# Isolators_HV_6W.net
KiCad netlist of a schematic drawn in Altium Designer
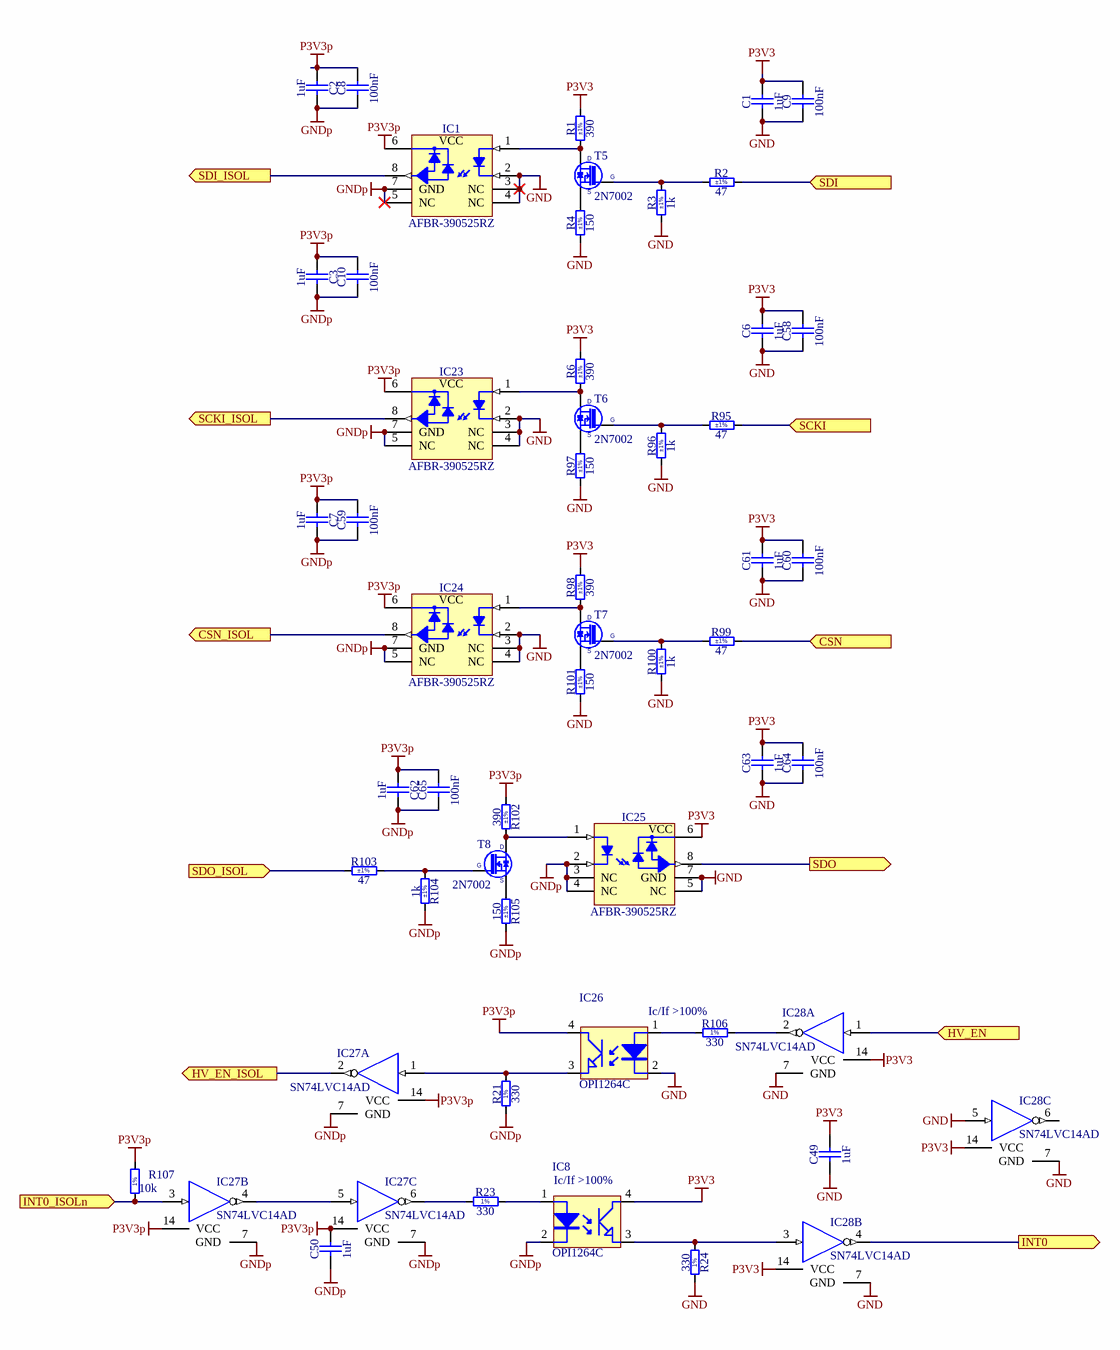
[diagram p0: Isolators_HV_6W.SchDoc]

(export (version "E")
  (design (tool "Eeschema 10.0.6"))
  (components
    (comp (ref "C1")
      (value "1uF")
      (footprint "CAPC1005X55N")
      (description "Non-polarised capacitor")
      (fields
        (field (name "PART NUMBER") "CC0402_1UF_16V_10%_X5R")
        (field (name "VOLTAGE") "16V")
        (field (name "AUTHOR") "CERN DEM JLC")
      )
      (libsource (lib "Capacitors") (part "Capacitor - non polarized"))
    )
    (comp (ref "C2")
      (value "1uF")
      (footprint "CAPC1005X55N")
      (description "Non-polarised capacitor")
      (fields
        (field (name "PART NUMBER") "CC0402_1UF_16V_10%_X5R")
        (field (name "VOLTAGE") "16V")
        (field (name "AUTHOR") "CERN DEM JLC")
      )
      (libsource (lib "Capacitors") (part "Capacitor - non polarized"))
    )
    (comp (ref "C3")
      (value "1uF")
      (footprint "CAPC1005X55N")
      (description "Non-polarised capacitor")
      (fields
        (field (name "PART NUMBER") "CC0402_1UF_16V_10%_X5R")
        (field (name "VOLTAGE") "16V")
        (field (name "AUTHOR") "CERN DEM JLC")
      )
      (libsource (lib "Capacitors") (part "Capacitor - non polarized"))
    )
    (comp (ref "C6")
      (value "1uF")
      (footprint "CAPC1005X55N")
      (description "Non-polarised capacitor")
      (fields
        (field (name "PART NUMBER") "CC0402_1UF_16V_10%_X5R")
        (field (name "VOLTAGE") "16V")
        (field (name "AUTHOR") "CERN DEM JLC")
      )
      (libsource (lib "Capacitors") (part "Capacitor - non polarized"))
    )
    (comp (ref "C7")
      (value "1uF")
      (footprint "CAPC1005X55N")
      (description "Non-polarised capacitor")
      (fields
        (field (name "PART NUMBER") "CC0402_1UF_16V_10%_X5R")
        (field (name "VOLTAGE") "16V")
        (field (name "AUTHOR") "CERN DEM JLC")
      )
      (libsource (lib "Capacitors") (part "Capacitor - non polarized"))
    )
    (comp (ref "C8")
      (value "100nF")
      (footprint "CAPC1005X55N")
      (description "Non-polarised capacitor")
      (fields
        (field (name "PART NUMBER") "CC0402_100NF_16V_10%_X5R")
        (field (name "VOLTAGE") "16V")
        (field (name "AUTHOR") "CERN DEM JLC")
      )
      (libsource (lib "Capacitors") (part "Capacitor - non polarized"))
    )
    (comp (ref "C9")
      (value "100nF")
      (footprint "CAPC1005X55N")
      (description "Non-polarised capacitor")
      (fields
        (field (name "PART NUMBER") "CC0402_100NF_16V_10%_X5R")
        (field (name "VOLTAGE") "16V")
        (field (name "AUTHOR") "CERN DEM JLC")
      )
      (libsource (lib "Capacitors") (part "Capacitor - non polarized"))
    )
    (comp (ref "C10")
      (value "100nF")
      (footprint "CAPC1005X55N")
      (description "Non-polarised capacitor")
      (fields
        (field (name "PART NUMBER") "CC0402_100NF_16V_10%_X5R")
        (field (name "VOLTAGE") "16V")
        (field (name "AUTHOR") "CERN DEM JLC")
      )
      (libsource (lib "Capacitors") (part "Capacitor - non polarized"))
    )
    (comp (ref "C49")
      (value "1uF")
      (footprint "CAPC1005X55N")
      (description "Non-polarised capacitor")
      (fields
        (field (name "PART NUMBER") "CC0402_1UF_16V_10%_X5R")
        (field (name "VOLTAGE") "16V")
        (field (name "AUTHOR") "CERN DEM JLC")
      )
      (libsource (lib "Capacitors") (part "Capacitor - non polarized"))
    )
    (comp (ref "C50")
      (value "1uF")
      (footprint "CAPC1005X55N")
      (description "Non-polarised capacitor")
      (fields
        (field (name "PART NUMBER") "CC0402_1UF_16V_10%_X5R")
        (field (name "VOLTAGE") "16V")
        (field (name "AUTHOR") "CERN DEM JLC")
      )
      (libsource (lib "Capacitors") (part "Capacitor - non polarized"))
    )
    (comp (ref "C58")
      (value "100nF")
      (footprint "CAPC1005X55N")
      (description "Non-polarised capacitor")
      (fields
        (field (name "PART NUMBER") "CC0402_100NF_16V_10%_X5R")
        (field (name "VOLTAGE") "16V")
        (field (name "AUTHOR") "CERN DEM JLC")
      )
      (libsource (lib "Capacitors") (part "Capacitor - non polarized"))
    )
    (comp (ref "C59")
      (value "100nF")
      (footprint "CAPC1005X55N")
      (description "Non-polarised capacitor")
      (fields
        (field (name "PART NUMBER") "CC0402_100NF_16V_10%_X5R")
        (field (name "VOLTAGE") "16V")
        (field (name "AUTHOR") "CERN DEM JLC")
      )
      (libsource (lib "Capacitors") (part "Capacitor - non polarized"))
    )
    (comp (ref "C60")
      (value "100nF")
      (footprint "CAPC1005X55N")
      (description "Non-polarised capacitor")
      (fields
        (field (name "PART NUMBER") "CC0402_100NF_16V_10%_X5R")
        (field (name "VOLTAGE") "16V")
        (field (name "AUTHOR") "CERN DEM JLC")
      )
      (libsource (lib "Capacitors") (part "Capacitor - non polarized"))
    )
    (comp (ref "C61")
      (value "1uF")
      (footprint "CAPC1005X55N")
      (description "Non-polarised capacitor")
      (fields
        (field (name "PART NUMBER") "CC0402_1UF_16V_10%_X5R")
        (field (name "VOLTAGE") "16V")
        (field (name "AUTHOR") "CERN DEM JLC")
      )
      (libsource (lib "Capacitors") (part "Capacitor - non polarized"))
    )
    (comp (ref "C62")
      (value "1uF")
      (footprint "CAPC1005X55N")
      (description "Non-polarised capacitor")
      (fields
        (field (name "PART NUMBER") "CC0402_1UF_16V_10%_X5R")
        (field (name "VOLTAGE") "16V")
        (field (name "AUTHOR") "CERN DEM JLC")
      )
      (libsource (lib "Capacitors") (part "Capacitor - non polarized"))
    )
    (comp (ref "C63")
      (value "1uF")
      (footprint "CAPC1005X55N")
      (description "Non-polarised capacitor")
      (fields
        (field (name "PART NUMBER") "CC0402_1UF_16V_10%_X5R")
        (field (name "VOLTAGE") "16V")
        (field (name "AUTHOR") "CERN DEM JLC")
      )
      (libsource (lib "Capacitors") (part "Capacitor - non polarized"))
    )
    (comp (ref "C64")
      (value "100nF")
      (footprint "CAPC1005X55N")
      (description "Non-polarised capacitor")
      (fields
        (field (name "PART NUMBER") "CC0402_100NF_16V_10%_X5R")
        (field (name "VOLTAGE") "16V")
        (field (name "AUTHOR") "CERN DEM JLC")
      )
      (libsource (lib "Capacitors") (part "Capacitor - non polarized"))
    )
    (comp (ref "C65")
      (value "100nF")
      (footprint "CAPC1005X55N")
      (description "Non-polarised capacitor")
      (fields
        (field (name "PART NUMBER") "CC0402_100NF_16V_10%_X5R")
        (field (name "VOLTAGE") "16V")
        (field (name "AUTHOR") "CERN DEM JLC")
      )
      (libsource (lib "Capacitors") (part "Capacitor - non polarized"))
    )
    (comp (ref "IC1")
      (value "AFBR-390525RZ")
      (footprint "BROADCOM_AFBR-390525RZ")
      (description "High Voltage Galvanic Insulation Link for DC to 5MBaud")
      (fields (field (name "MANUFACTURER") "BROADCOM") (field (name "AUTHOR") "CERN DEM HF"))
      (libsource (lib "") (part "AFBR-3905XXRZ_1"))
    )
    (comp (ref "IC8")
      (value "OPI1264C")
      (footprint "OPI1264C")
      (description "10kV opto-coupler")
      (libsource (lib "LIBRARY_SCH") (part "OPTO-OPI1264C"))
    )
    (comp (ref "IC23")
      (value "AFBR-390525RZ")
      (footprint "BROADCOM_AFBR-390525RZ")
      (description "High Voltage Galvanic Insulation Link for DC to 5MBaud")
      (fields (field (name "MANUFACTURER") "BROADCOM") (field (name "AUTHOR") "CERN DEM HF"))
      (libsource (lib "") (part "AFBR-3905XXRZ_1"))
    )
    (comp (ref "IC24")
      (value "AFBR-390525RZ")
      (footprint "BROADCOM_AFBR-390525RZ")
      (description "High Voltage Galvanic Insulation Link for DC to 5MBaud")
      (fields (field (name "MANUFACTURER") "BROADCOM") (field (name "AUTHOR") "CERN DEM HF"))
      (libsource (lib "") (part "AFBR-3905XXRZ_1"))
    )
    (comp (ref "IC25")
      (value "AFBR-390525RZ")
      (footprint "BROADCOM_AFBR-390525RZ")
      (description "High Voltage Galvanic Insulation Link for DC to 5MBaud")
      (fields (field (name "MANUFACTURER") "BROADCOM") (field (name "AUTHOR") "CERN DEM HF"))
      (libsource (lib "ICs And Semiconductors") (part "AFBR-3905XXRZ"))
    )
    (comp (ref "IC26")
      (value "OPI1264C")
      (footprint "OPI1264C")
      (description "10kV opto-coupler")
      (libsource (lib "") (part "OPTO-OPI1264C_1"))
    )
    (comp (ref "IC27")
      (value "SN74LVC14AD")
      (footprint "SOIC127P600X175-14N")
      (description "Hex Schmitt-Trigger Inverter")
      (fields (field (name "MANUFACTURER") "TEXAS INSTRUMENTS") (field (name "AUTHOR") "CERN DEM JMW"))
      (libsource (lib "ICs And Semiconductors") (part "7414"))
    )
    (comp (ref "IC28")
      (value "SN74LVC14AD")
      (footprint "SOIC127P600X175-14N")
      (description "Hex Schmitt-Trigger Inverter")
      (fields (field (name "MANUFACTURER") "TEXAS INSTRUMENTS") (field (name "AUTHOR") "CERN DEM JMW"))
      (libsource (lib "ICs And Semiconductors") (part "7414"))
    )
    (comp (ref "R1")
      (value "390")
      (footprint "RESC1608X55N")
      (description "Resistor - 1%")
      (fields
        (field (name "TOLERANCE") "±1%")
        (field (name "PART NUMBER") "R0603_390R_1%_0.1W_100PPM")
        (field (name "POWER") "0.1W")
        (field (name "AUTHOR") "CERN DEM JLC")
      )
      (libsource (lib "Resistors") (part "Resistor - 1%"))
    )
    (comp (ref "R2")
      (value "47")
      (footprint "RESC1005X40N")
      (description "Resistor - 1%")
      (fields
        (field (name "TOLERANCE") "±1%")
        (field (name "PART NUMBER") "R0402_47R_1%_0.0625W_100PPM")
        (field (name "POWER") "0.0625W")
        (field (name "AUTHOR") "CERN DEM JLC")
      )
      (libsource (lib "Resistors") (part "Resistor - 1%"))
    )
    (comp (ref "R3")
      (value "1k")
      (footprint "RESC1005X40N")
      (description "Resistor - 1%")
      (fields
        (field (name "TOLERANCE") "±1%")
        (field (name "PART NUMBER") "R0402_1K_1%_0.0625W_100PPM")
        (field (name "POWER") "0.0625W")
        (field (name "AUTHOR") "CERN DEM JLC")
      )
      (libsource (lib "Resistors") (part "Resistor - 1%"))
    )
    (comp (ref "R4")
      (value "150")
      (footprint "RESC1608X55N")
      (description "Resistor - 1%")
      (fields
        (field (name "TOLERANCE") "±1%")
        (field (name "PART NUMBER") "R0603_150R_1%_0.1W_100PPM")
        (field (name "POWER") "0.1W")
        (field (name "AUTHOR") "CERN DEM JLC")
      )
      (libsource (lib "Resistors") (part "Resistor - 1%"))
    )
    (comp (ref "R6")
      (value "390")
      (footprint "RESC1608X55N")
      (description "Resistor - 1%")
      (fields
        (field (name "TOLERANCE") "±1%")
        (field (name "PART NUMBER") "R0603_390R_1%_0.1W_100PPM")
        (field (name "POWER") "0.1W")
        (field (name "AUTHOR") "CERN DEM JLC")
      )
      (libsource (lib "Resistors") (part "Resistor - 1%"))
    )
    (comp (ref "R21")
      (value "330")
      (footprint "RESC1005X40N")
      (description "Resistor - 1%")
      (fields
        (field (name "PART NUMBER") "R0402_330R_1%_0.0625W_100PPM")
        (field (name "POWER") "0.0625W")
        (field (name "AUTHOR") "CERN DEM JLC")
      )
      (libsource (lib "") (part "Resistor - 1%_1"))
    )
    (comp (ref "R23")
      (value "330")
      (footprint "RESC1005X40N")
      (description "Resistor - 1%")
      (fields
        (field (name "PART NUMBER") "R0402_330R_1%_0.0625W_100PPM")
        (field (name "POWER") "0.0625W")
        (field (name "AUTHOR") "CERN DEM JLC")
      )
      (libsource (lib "") (part "Resistor - 1%_1"))
    )
    (comp (ref "R24")
      (value "330")
      (footprint "RESC1005X40N")
      (description "Resistor - 1%")
      (fields
        (field (name "PART NUMBER") "R0402_330R_1%_0.0625W_100PPM")
        (field (name "POWER") "0.0625W")
        (field (name "AUTHOR") "CERN DEM JLC")
      )
      (libsource (lib "") (part "Resistor - 1%_1"))
    )
    (comp (ref "R95")
      (value "47")
      (footprint "RESC1005X40N")
      (description "Resistor - 1%")
      (fields
        (field (name "TOLERANCE") "±1%")
        (field (name "PART NUMBER") "R0402_47R_1%_0.0625W_100PPM")
        (field (name "POWER") "0.0625W")
        (field (name "AUTHOR") "CERN DEM JLC")
      )
      (libsource (lib "Resistors") (part "Resistor - 1%"))
    )
    (comp (ref "R96")
      (value "1k")
      (footprint "RESC1005X40N")
      (description "Resistor - 1%")
      (fields
        (field (name "TOLERANCE") "±1%")
        (field (name "PART NUMBER") "R0402_1K_1%_0.0625W_100PPM")
        (field (name "POWER") "0.0625W")
        (field (name "AUTHOR") "CERN DEM JLC")
      )
      (libsource (lib "Resistors") (part "Resistor - 1%"))
    )
    (comp (ref "R97")
      (value "150")
      (footprint "RESC1608X55N")
      (description "Resistor - 1%")
      (fields
        (field (name "TOLERANCE") "±1%")
        (field (name "PART NUMBER") "R0603_150R_1%_0.1W_100PPM")
        (field (name "POWER") "0.1W")
        (field (name "AUTHOR") "CERN DEM JLC")
      )
      (libsource (lib "Resistors") (part "Resistor - 1%"))
    )
    (comp (ref "R98")
      (value "390")
      (footprint "RESC1608X55N")
      (description "Resistor - 1%")
      (fields
        (field (name "TOLERANCE") "±1%")
        (field (name "PART NUMBER") "R0603_390R_1%_0.1W_100PPM")
        (field (name "POWER") "0.1W")
        (field (name "AUTHOR") "CERN DEM JLC")
      )
      (libsource (lib "Resistors") (part "Resistor - 1%"))
    )
    (comp (ref "R99")
      (value "47")
      (footprint "RESC1005X40N")
      (description "Resistor - 1%")
      (fields
        (field (name "TOLERANCE") "±1%")
        (field (name "PART NUMBER") "R0402_47R_1%_0.0625W_100PPM")
        (field (name "POWER") "0.0625W")
        (field (name "AUTHOR") "CERN DEM JLC")
      )
      (libsource (lib "Resistors") (part "Resistor - 1%"))
    )
    (comp (ref "R100")
      (value "1k")
      (footprint "RESC1005X40N")
      (description "Resistor - 1%")
      (fields
        (field (name "TOLERANCE") "±1%")
        (field (name "PART NUMBER") "R0402_1K_1%_0.0625W_100PPM")
        (field (name "POWER") "0.0625W")
        (field (name "AUTHOR") "CERN DEM JLC")
      )
      (libsource (lib "Resistors") (part "Resistor - 1%"))
    )
    (comp (ref "R101")
      (value "150")
      (footprint "RESC1608X55N")
      (description "Resistor - 1%")
      (fields
        (field (name "TOLERANCE") "±1%")
        (field (name "PART NUMBER") "R0603_150R_1%_0.1W_100PPM")
        (field (name "POWER") "0.1W")
        (field (name "AUTHOR") "CERN DEM JLC")
      )
      (libsource (lib "Resistors") (part "Resistor - 1%"))
    )
    (comp (ref "R102")
      (value "390")
      (footprint "RESC1608X55N")
      (description "Resistor - 1%")
      (fields
        (field (name "TOLERANCE") "±1%")
        (field (name "PART NUMBER") "R0603_390R_1%_0.1W_100PPM")
        (field (name "POWER") "0.1W")
        (field (name "AUTHOR") "CERN DEM JLC")
      )
      (libsource (lib "Resistors") (part "Resistor - 1%"))
    )
    (comp (ref "R103")
      (value "47")
      (footprint "RESC1005X40N")
      (description "Resistor - 1%")
      (fields
        (field (name "TOLERANCE") "±1%")
        (field (name "PART NUMBER") "R0402_47R_1%_0.0625W_100PPM")
        (field (name "POWER") "0.0625W")
        (field (name "AUTHOR") "CERN DEM JLC")
      )
      (libsource (lib "Resistors") (part "Resistor - 1%"))
    )
    (comp (ref "R104")
      (value "1k")
      (footprint "RESC1005X40N")
      (description "Resistor - 1%")
      (fields
        (field (name "TOLERANCE") "±1%")
        (field (name "PART NUMBER") "R0402_1K_1%_0.0625W_100PPM")
        (field (name "POWER") "0.0625W")
        (field (name "AUTHOR") "CERN DEM JLC")
      )
      (libsource (lib "Resistors") (part "Resistor - 1%"))
    )
    (comp (ref "R105")
      (value "150")
      (footprint "RESC1608X55N")
      (description "Resistor - 1%")
      (fields
        (field (name "TOLERANCE") "±1%")
        (field (name "PART NUMBER") "R0603_150R_1%_0.1W_100PPM")
        (field (name "POWER") "0.1W")
        (field (name "AUTHOR") "CERN DEM JLC")
      )
      (libsource (lib "Resistors") (part "Resistor - 1%"))
    )
    (comp (ref "R106")
      (value "330")
      (footprint "RESC1005X40N")
      (description "Resistor - 1%")
      (fields
        (field (name "PART NUMBER") "R0402_330R_1%_0.0625W_100PPM")
        (field (name "POWER") "0.0625W")
        (field (name "AUTHOR") "CERN DEM JLC")
      )
      (libsource (lib "") (part "Resistor - 1%_1"))
    )
    (comp (ref "R107")
      (value "10k")
      (footprint "RESC1005X40N")
      (description "Resistor - 1%")
      (fields
        (field (name "PART NUMBER") "R0402_10K_1%_0.0625W_100PPM")
        (field (name "POWER") "0.0625W")
        (field (name "AUTHOR") "CERN DEM JLC")
      )
      (libsource (lib "") (part "Resistor - 1%_1"))
    )
    (comp (ref "T5")
      (value "2N7002")
      (footprint "SOT95P240X130-3N")
      (description "N-CHANNEL MOSFET WITH DIODE")
      (fields (field (name "MANUFACTURER") "FAIRCHILD SEMICONDUCTOR") (field (name "AUTHOR") "CERN DEM JLC"))
      (libsource (lib "") (part "N-MOSFET-D 1G 2S 3D_1"))
    )
    (comp (ref "T6")
      (value "2N7002")
      (footprint "SOT95P240X130-3N")
      (description "N-CHANNEL MOSFET WITH DIODE")
      (fields (field (name "MANUFACTURER") "FAIRCHILD SEMICONDUCTOR") (field (name "AUTHOR") "CERN DEM JLC"))
      (libsource (lib "") (part "N-MOSFET-D 1G 2S 3D_1"))
    )
    (comp (ref "T7")
      (value "2N7002")
      (footprint "SOT95P240X130-3N")
      (description "N-CHANNEL MOSFET WITH DIODE")
      (fields (field (name "MANUFACTURER") "FAIRCHILD SEMICONDUCTOR") (field (name "AUTHOR") "CERN DEM JLC"))
      (libsource (lib "") (part "N-MOSFET-D 1G 2S 3D_1"))
    )
    (comp (ref "T8")
      (value "2N7002")
      (footprint "SOT95P240X130-3N")
      (description "N-CHANNEL MOSFET WITH DIODE")
      (fields (field (name "MANUFACTURER") "FAIRCHILD SEMICONDUCTOR") (field (name "AUTHOR") "CERN DEM JLC"))
      (libsource (lib "ICs And Semiconductors") (part "N-MOSFET-D 1G 2S 3D"))
    )
  )
  (nets
    (net (code "1") (name "/CSN") (class "Default")
      (node (ref "R99") (pin "2") (pinfunction "2_2") (pintype "passive"))
    )
    (net (code "2") (name "/CSN_ISOL") (class "Default")
      (node (ref "IC24") (pin "8") (pinfunction "DATA_OUT_8") (pintype "output"))
    )
    (net (code "3") (name "/HV_EN") (class "Default")
      (node (ref "IC28") (pin "1") (pinfunction "IN_1") (pintype "input"))
    )
    (net (code "4") (name "/HV_EN_ISOL") (class "Default")
      (node (ref "IC27") (pin "2") (pinfunction "OUT_2") (pintype "output"))
    )
    (net (code "5") (name "/INT0") (class "Default")
      (node (ref "IC28") (pin "4") (pinfunction "OUT_4") (pintype "output"))
    )
    (net (code "6") (name "/INT0_ISOLn") (class "Default")
      (node (ref "IC27") (pin "3") (pinfunction "IN_3") (pintype "input"))
      (node (ref "R107") (pin "1") (pinfunction "1_1") (pintype "passive"))
    )
    (net (code "7") (name "/SCKI") (class "Default")
      (node (ref "R95") (pin "2") (pinfunction "2_2") (pintype "passive"))
    )
    (net (code "8") (name "/SCKI_ISOL") (class "Default")
      (node (ref "IC23") (pin "8") (pinfunction "DATA_OUT_8") (pintype "output"))
    )
    (net (code "9") (name "/SDI") (class "Default")
      (node (ref "R2") (pin "2") (pinfunction "2_2") (pintype "passive"))
    )
    (net (code "10") (name "/SDI_ISOL") (class "Default")
      (node (ref "IC1") (pin "8") (pinfunction "DATA_OUT_8") (pintype "output"))
    )
    (net (code "11") (name "/SDO") (class "Default")
      (node (ref "IC25") (pin "8") (pinfunction "DATA_OUT_8") (pintype "output"))
    )
    (net (code "12") (name "/SDO_ISOL") (class "Default")
      (node (ref "R103") (pin "2") (pinfunction "2_2") (pintype "passive"))
    )
    (net (code "13") (name "GND") (class "Default")
      (node (ref "C1") (pin "1") (pinfunction "1_1") (pintype "passive"))
      (node (ref "C49") (pin "2") (pinfunction "2_2") (pintype "passive"))
      (node (ref "C58") (pin "1") (pinfunction "1_1") (pintype "passive"))
      (node (ref "C6") (pin "1") (pinfunction "1_1") (pintype "passive"))
      (node (ref "C60") (pin "1") (pinfunction "1_1") (pintype "passive"))
      (node (ref "C61") (pin "1") (pinfunction "1_1") (pintype "passive"))
      (node (ref "C63") (pin "2") (pinfunction "2_2") (pintype "passive"))
      (node (ref "C64") (pin "1") (pinfunction "1_1") (pintype "passive"))
      (node (ref "C9") (pin "1") (pinfunction "1_1") (pintype "passive"))
      (node (ref "IC1") (pin "2") (pinfunction "C_2") (pintype "input"))
      (node (ref "IC1") (pin "3") (pinfunction "NC_3") (pintype "open_collector"))
      (node (ref "IC1") (pin "4") (pinfunction "NC_4") (pintype "open_collector"))
      (node (ref "IC23") (pin "2") (pinfunction "C_2") (pintype "input"))
      (node (ref "IC23") (pin "3") (pinfunction "NC_3") (pintype "open_collector"))
      (node (ref "IC23") (pin "4") (pinfunction "NC_4") (pintype "open_collector"))
      (node (ref "IC24") (pin "2") (pinfunction "C_2") (pintype "input"))
      (node (ref "IC24") (pin "3") (pinfunction "NC_3") (pintype "open_collector"))
      (node (ref "IC24") (pin "4") (pinfunction "NC_4") (pintype "open_collector"))
      (node (ref "IC25") (pin "5") (pinfunction "NC_5") (pintype "open_collector"))
      (node (ref "IC25") (pin "7") (pinfunction "GND_7") (pintype "power_in"))
      (node (ref "IC26") (pin "2") (pinfunction "K_2") (pintype "passive"))
      (node (ref "IC28") (pin "5") (pinfunction "IN_5") (pintype "input"))
      (node (ref "IC28") (pin "7") (pinfunction "GND_7") (pintype "power_in"))
      (node (ref "R100") (pin "1") (pinfunction "1_1") (pintype "passive"))
      (node (ref "R101") (pin "1") (pinfunction "1_1") (pintype "passive"))
      (node (ref "R24") (pin "1") (pinfunction "1_1") (pintype "passive"))
      (node (ref "R3") (pin "1") (pinfunction "1_1") (pintype "passive"))
      (node (ref "R4") (pin "1") (pinfunction "1_1") (pintype "passive"))
      (node (ref "R96") (pin "1") (pinfunction "1_1") (pintype "passive"))
      (node (ref "R97") (pin "1") (pinfunction "1_1") (pintype "passive"))
    )
    (net (code "14") (name "GNDp") (class "Default")
      (node (ref "C10") (pin "1") (pinfunction "1_1") (pintype "passive"))
      (node (ref "C2") (pin "2") (pinfunction "2_2") (pintype "passive"))
      (node (ref "C3") (pin "2") (pinfunction "2_2") (pintype "passive"))
      (node (ref "C50") (pin "2") (pinfunction "2_2") (pintype "passive"))
      (node (ref "C59") (pin "1") (pinfunction "1_1") (pintype "passive"))
      (node (ref "C62") (pin "1") (pinfunction "1_1") (pintype "passive"))
      (node (ref "C65") (pin "1") (pinfunction "1_1") (pintype "passive"))
      (node (ref "C7") (pin "2") (pinfunction "2_2") (pintype "passive"))
      (node (ref "C8") (pin "1") (pinfunction "1_1") (pintype "passive"))
      (node (ref "IC1") (pin "5") (pinfunction "NC_5") (pintype "open_collector"))
      (node (ref "IC1") (pin "7") (pinfunction "GND_7") (pintype "power_in"))
      (node (ref "IC23") (pin "5") (pinfunction "NC_5") (pintype "open_collector"))
      (node (ref "IC23") (pin "7") (pinfunction "GND_7") (pintype "power_in"))
      (node (ref "IC24") (pin "5") (pinfunction "NC_5") (pintype "open_collector"))
      (node (ref "IC24") (pin "7") (pinfunction "GND_7") (pintype "power_in"))
      (node (ref "IC25") (pin "2") (pinfunction "C_2") (pintype "input"))
      (node (ref "IC25") (pin "3") (pinfunction "NC_3") (pintype "open_collector"))
      (node (ref "IC25") (pin "4") (pinfunction "NC_4") (pintype "open_collector"))
      (node (ref "IC27") (pin "7") (pinfunction "GND_7") (pintype "power_in"))
      (node (ref "IC8") (pin "2") (pinfunction "K_2") (pintype "passive"))
      (node (ref "R104") (pin "1") (pinfunction "1_1") (pintype "passive"))
      (node (ref "R105") (pin "1") (pinfunction "1_1") (pintype "passive"))
      (node (ref "R21") (pin "1") (pinfunction "1_1") (pintype "passive"))
    )
    (net (code "15") (name "Net-(IC1-A)") (class "Default")
      (node (ref "IC1") (pin "1") (pinfunction "A_1") (pintype "input"))
      (node (ref "R1") (pin "1") (pinfunction "1_1") (pintype "passive"))
      (node (ref "T5") (pin "3") (pinfunction "D_3") (pintype "passive"))
    )
    (net (code "16") (name "Net-(IC8-A)") (class "Default")
      (node (ref "IC8") (pin "1") (pinfunction "A_1") (pintype "passive"))
      (node (ref "R23") (pin "1") (pinfunction "1_1") (pintype "passive"))
    )
    (net (code "17") (name "Net-(IC23-A)") (class "Default")
      (node (ref "IC23") (pin "1") (pinfunction "A_1") (pintype "input"))
      (node (ref "R6") (pin "1") (pinfunction "1_1") (pintype "passive"))
      (node (ref "T6") (pin "3") (pinfunction "D_3") (pintype "passive"))
    )
    (net (code "18") (name "Net-(IC24-A)") (class "Default")
      (node (ref "IC24") (pin "1") (pinfunction "A_1") (pintype "input"))
      (node (ref "R98") (pin "1") (pinfunction "1_1") (pintype "passive"))
      (node (ref "T7") (pin "3") (pinfunction "D_3") (pintype "passive"))
    )
    (net (code "19") (name "Net-(IC25-A)") (class "Default")
      (node (ref "IC25") (pin "1") (pinfunction "A_1") (pintype "input"))
      (node (ref "R102") (pin "1") (pinfunction "1_1") (pintype "passive"))
      (node (ref "T8") (pin "3") (pinfunction "D_3") (pintype "passive"))
    )
    (net (code "20") (name "Net-(IC26-A)") (class "Default")
      (node (ref "IC26") (pin "1") (pinfunction "A_1") (pintype "passive"))
      (node (ref "R106") (pin "1") (pinfunction "1_1") (pintype "passive"))
    )
    (net (code "21") (name "Net-(IC26-E)") (class "Default")
      (node (ref "IC26") (pin "3") (pinfunction "E_3") (pintype "passive"))
      (node (ref "IC27") (pin "1") (pinfunction "IN_1") (pintype "input"))
      (node (ref "R21") (pin "2") (pinfunction "2_2") (pintype "passive"))
    )
    (net (code "22") (name "Net-(IC27B-OUT)") (class "Default")
      (node (ref "IC27") (pin "4") (pinfunction "OUT_4") (pintype "output"))
      (node (ref "IC27") (pin "5") (pinfunction "IN_5") (pintype "input"))
    )
    (net (code "23") (name "Net-(IC27C-OUT)") (class "Default")
      (node (ref "IC27") (pin "6") (pinfunction "OUT_6") (pintype "output"))
      (node (ref "R23") (pin "2") (pinfunction "2_2") (pintype "passive"))
    )
    (net (code "24") (name "Net-(IC28A-OUT)") (class "Default")
      (node (ref "IC28") (pin "2") (pinfunction "OUT_2") (pintype "output"))
      (node (ref "R106") (pin "2") (pinfunction "2_2") (pintype "passive"))
    )
    (net (code "25") (name "Net-(IC28B-IN)") (class "Default")
      (node (ref "IC28") (pin "3") (pinfunction "IN_3") (pintype "input"))
      (node (ref "IC8") (pin "3") (pinfunction "E_3") (pintype "passive"))
      (node (ref "R24") (pin "2") (pinfunction "2_2") (pintype "passive"))
    )
    (net (code "26") (name "Net-(T5-G)") (class "Default")
      (node (ref "R2") (pin "1") (pinfunction "1_1") (pintype "passive"))
      (node (ref "R3") (pin "2") (pinfunction "2_2") (pintype "passive"))
      (node (ref "T5") (pin "1") (pinfunction "G_1") (pintype "passive"))
    )
    (net (code "27") (name "Net-(T5-S)") (class "Default")
      (node (ref "R4") (pin "2") (pinfunction "2_2") (pintype "passive"))
      (node (ref "T5") (pin "2") (pinfunction "S_2") (pintype "passive"))
    )
    (net (code "28") (name "Net-(T6-G)") (class "Default")
      (node (ref "R95") (pin "1") (pinfunction "1_1") (pintype "passive"))
      (node (ref "R96") (pin "2") (pinfunction "2_2") (pintype "passive"))
      (node (ref "T6") (pin "1") (pinfunction "G_1") (pintype "passive"))
    )
    (net (code "29") (name "Net-(T6-S)") (class "Default")
      (node (ref "R97") (pin "2") (pinfunction "2_2") (pintype "passive"))
      (node (ref "T6") (pin "2") (pinfunction "S_2") (pintype "passive"))
    )
    (net (code "30") (name "Net-(T7-G)") (class "Default")
      (node (ref "R100") (pin "2") (pinfunction "2_2") (pintype "passive"))
      (node (ref "R99") (pin "1") (pinfunction "1_1") (pintype "passive"))
      (node (ref "T7") (pin "1") (pinfunction "G_1") (pintype "passive"))
    )
    (net (code "31") (name "Net-(T7-S)") (class "Default")
      (node (ref "R101") (pin "2") (pinfunction "2_2") (pintype "passive"))
      (node (ref "T7") (pin "2") (pinfunction "S_2") (pintype "passive"))
    )
    (net (code "32") (name "Net-(T8-G)") (class "Default")
      (node (ref "R103") (pin "1") (pinfunction "1_1") (pintype "passive"))
      (node (ref "R104") (pin "2") (pinfunction "2_2") (pintype "passive"))
      (node (ref "T8") (pin "1") (pinfunction "G_1") (pintype "passive"))
    )
    (net (code "33") (name "Net-(T8-S)") (class "Default")
      (node (ref "R105") (pin "2") (pinfunction "2_2") (pintype "passive"))
      (node (ref "T8") (pin "2") (pinfunction "S_2") (pintype "passive"))
    )
    (net (code "34") (name "P3V3") (class "Default")
      (node (ref "C1") (pin "2") (pinfunction "2_2") (pintype "passive"))
      (node (ref "C49") (pin "1") (pinfunction "1_1") (pintype "passive"))
      (node (ref "C58") (pin "2") (pinfunction "2_2") (pintype "passive"))
      (node (ref "C6") (pin "2") (pinfunction "2_2") (pintype "passive"))
      (node (ref "C60") (pin "2") (pinfunction "2_2") (pintype "passive"))
      (node (ref "C61") (pin "2") (pinfunction "2_2") (pintype "passive"))
      (node (ref "C63") (pin "1") (pinfunction "1_1") (pintype "passive"))
      (node (ref "C64") (pin "2") (pinfunction "2_2") (pintype "passive"))
      (node (ref "C9") (pin "2") (pinfunction "2_2") (pintype "passive"))
      (node (ref "IC25") (pin "6") (pinfunction "VCC_6") (pintype "power_in"))
      (node (ref "IC28") (pin "14") (pinfunction "VCC_14") (pintype "power_in"))
      (node (ref "IC8") (pin "4") (pinfunction "C_4") (pintype "passive"))
      (node (ref "R1") (pin "2") (pinfunction "2_2") (pintype "passive"))
      (node (ref "R6") (pin "2") (pinfunction "2_2") (pintype "passive"))
      (node (ref "R98") (pin "2") (pinfunction "2_2") (pintype "passive"))
    )
    (net (code "35") (name "P3V3p") (class "Default")
      (node (ref "C10") (pin "2") (pinfunction "2_2") (pintype "passive"))
      (node (ref "C2") (pin "1") (pinfunction "1_1") (pintype "passive"))
      (node (ref "C3") (pin "1") (pinfunction "1_1") (pintype "passive"))
      (node (ref "C50") (pin "1") (pinfunction "1_1") (pintype "passive"))
      (node (ref "C59") (pin "2") (pinfunction "2_2") (pintype "passive"))
      (node (ref "C62") (pin "2") (pinfunction "2_2") (pintype "passive"))
      (node (ref "C65") (pin "2") (pinfunction "2_2") (pintype "passive"))
      (node (ref "C7") (pin "1") (pinfunction "1_1") (pintype "passive"))
      (node (ref "C8") (pin "2") (pinfunction "2_2") (pintype "passive"))
      (node (ref "IC1") (pin "6") (pinfunction "VCC_6") (pintype "power_in"))
      (node (ref "IC23") (pin "6") (pinfunction "VCC_6") (pintype "power_in"))
      (node (ref "IC24") (pin "6") (pinfunction "VCC_6") (pintype "power_in"))
      (node (ref "IC26") (pin "4") (pinfunction "C_4") (pintype "passive"))
      (node (ref "IC27") (pin "14") (pinfunction "VCC_14") (pintype "power_in"))
      (node (ref "R102") (pin "2") (pinfunction "2_2") (pintype "passive"))
      (node (ref "R107") (pin "2") (pinfunction "2_2") (pintype "passive"))
    )
    (net (code "36") (name "unconnected-(IC28C-OUT-Pad6)") (class "Default")
      (node (ref "IC28") (pin "6") (pinfunction "OUT_6") (pintype "output"))
    )
  )
)
